# AFE.net
KiCad netlist of a schematic drawn in Altium Designer
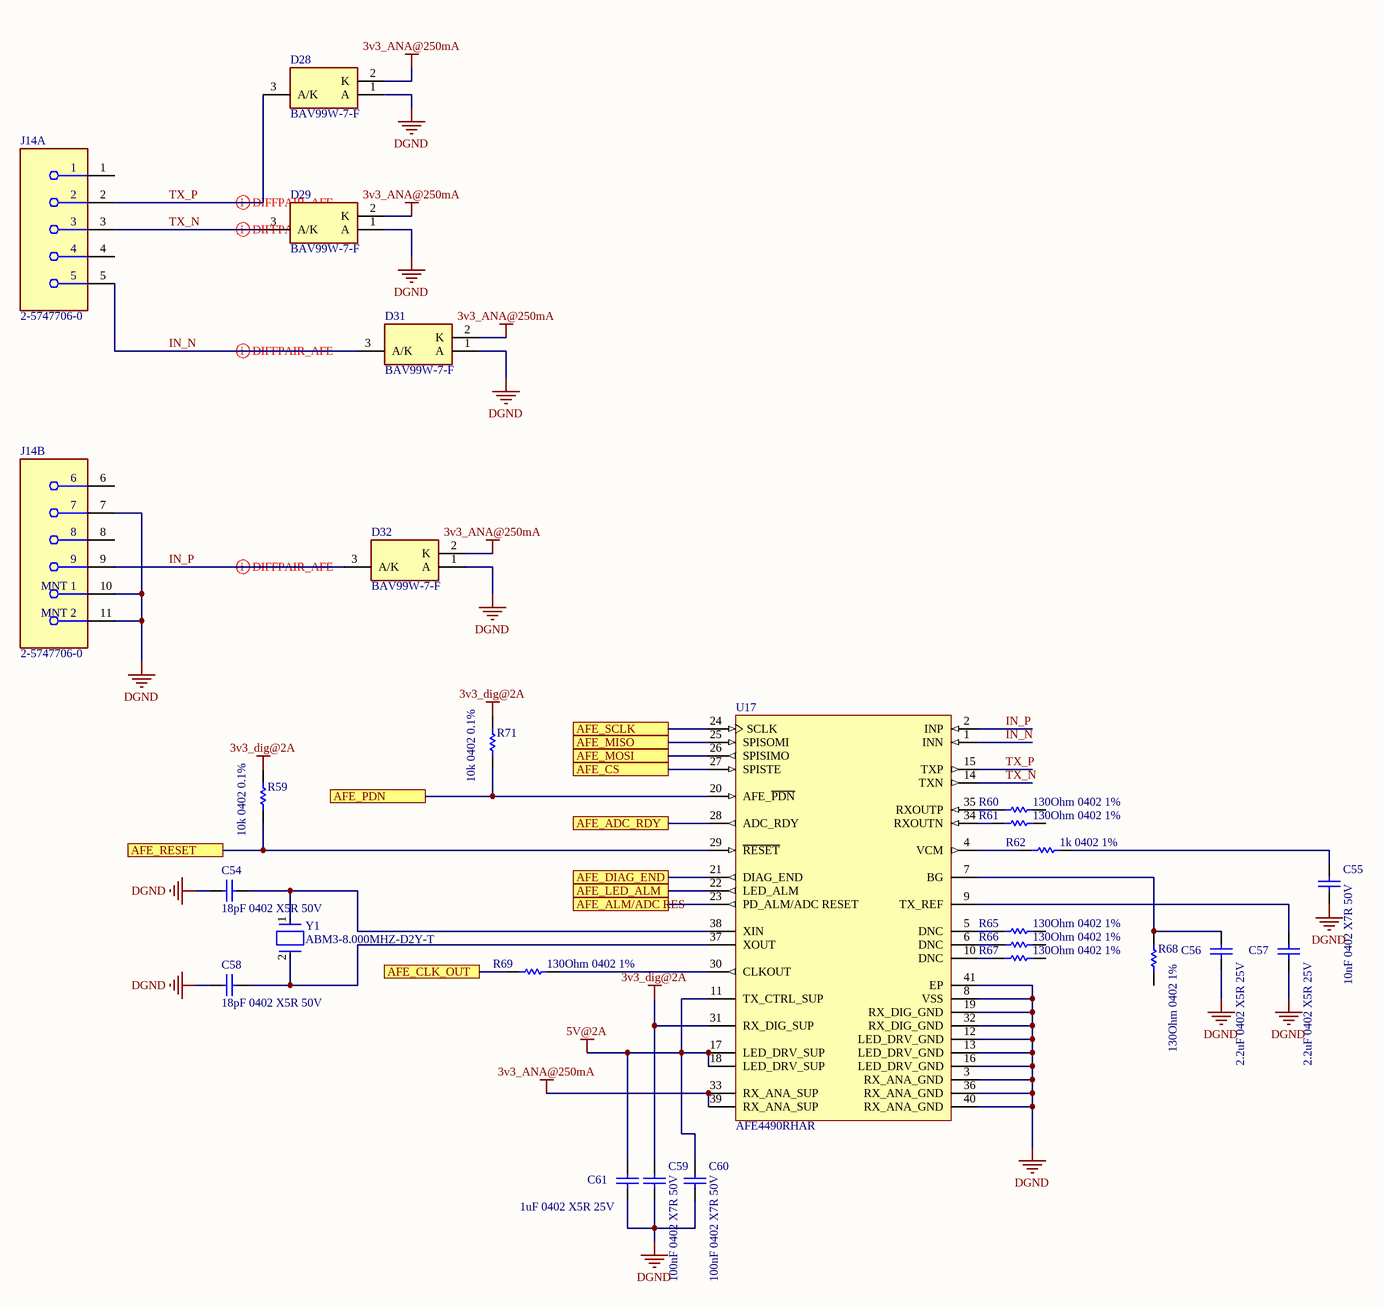
[diagram p0: AFE.SchDoc]

(export (version "E")
  (design (tool "Eeschema 10.0.6"))
  (components
    (comp (ref "C54")
      (value "18pF 0402 X5R 50V")
      (footprint "CAPC1005X55X25NL5T10")
      (libsource (lib "Altium Content Vault") (part "CAP-NP-2"))
    )
    (comp (ref "C55")
      (value "10nF 0402 X7R 50V")
      (footprint "CAPC1005X55X25NL5T10")
      (libsource (lib "Altium Content Vault") (part "CAP-NP-2"))
    )
    (comp (ref "C56")
      (value "2.2uF 0402 X5R 25V")
      (footprint "CAPC1005X55X25NL5T10")
      (libsource (lib "Altium Content Vault") (part "CAP-NP-2"))
    )
    (comp (ref "C57")
      (value "2.2uF 0402 X5R 25V")
      (footprint "CAPC1005X55X25NL5T10")
      (libsource (lib "Altium Content Vault") (part "CAP-NP-2"))
    )
    (comp (ref "C58")
      (value "18pF 0402 X5R 50V")
      (footprint "CAPC1005X55X25NL5T10")
      (libsource (lib "Altium Content Vault") (part "CAP-NP-2"))
    )
    (comp (ref "C59")
      (value "100nF 0402 X7R 50V")
      (footprint "CAPC1005X55X25NL5T10")
      (libsource (lib "Altium Content Vault") (part "CAP-NP-2"))
    )
    (comp (ref "C60")
      (value "100nF 0402 X7R 50V")
      (footprint "CAPC1005X55X25NL5T10")
      (libsource (lib "Altium Content Vault") (part "CAP-NP-2"))
    )
    (comp (ref "C61")
      (value "1uF 0402 X5R 25V")
      (footprint "CAPC1005X55X25NL5T10")
      (libsource (lib "Altium Content Vault") (part "CAP-NP-2"))
    )
    (comp (ref "D28")
      (value "BAV99W-7-F")
      (footprint "SamacSys:SOT65P210X110-3N")
      (description "Diode")
      (fields (field (name "MOUSER PART NUMBER") "621-BAV99W-F"))
      (libsource (lib "*") (part "BAV99W-7-F"))
    )
    (comp (ref "D29")
      (value "BAV99W-7-F")
      (footprint "SamacSys:SOT65P210X110-3N")
      (description "Diode")
      (fields (field (name "MOUSER PART NUMBER") "621-BAV99W-F"))
      (libsource (lib "*") (part "BAV99W-7-F"))
    )
    (comp (ref "D31")
      (value "BAV99W-7-F")
      (footprint "SamacSys:SOT65P210X110-3N")
      (description "Diode")
      (fields (field (name "MOUSER PART NUMBER") "621-BAV99W-F"))
      (libsource (lib "*") (part "BAV99W-7-F"))
    )
    (comp (ref "D32")
      (value "BAV99W-7-F")
      (footprint "SamacSys:SOT65P210X110-3N")
      (description "Diode")
      (fields (field (name "MOUSER PART NUMBER") "621-BAV99W-F"))
      (libsource (lib "*") (part "BAV99W-7-F"))
    )
    (comp (ref "J14")
      (value "2-5747706-0")
      (footprint "FP-2-5747706-0-MFG")
      (description "CONN D-SUB RCPT 9POS VERT SOLDER")
      (fields
        (field (name "OCTOPART") "https://octopart.com/2-5747706-0-te+connectivity-39499683")
        (field (name "MANUFACTURER") "TE Connectivity")
      )
      (libsource (lib "Altium Content Vault") (part "05b08df3a4487cf48e63ed58a2c51a6"))
    )
    (comp (ref "R59")
      (value "10k 0402 0.1%")
      (footprint "RESC1005X40X25ML05T10")
      (libsource (lib "Altium Content Vault") (part "RES"))
    )
    (comp (ref "R60")
      (value "130Ohm 0402 1%")
      (footprint "RESC1005X40X25ML05T10")
      (libsource (lib "Altium Content Vault") (part "RES"))
    )
    (comp (ref "R61")
      (value "130Ohm 0402 1%")
      (footprint "RESC1005X40X25ML05T10")
      (libsource (lib "Altium Content Vault") (part "RES"))
    )
    (comp (ref "R62")
      (value "1k 0402 1%")
      (footprint "RESC1005X40X25ML05T10")
      (libsource (lib "Altium Content Vault") (part "RES"))
    )
    (comp (ref "R65")
      (value "130Ohm 0402 1%")
      (footprint "RESC1005X40X25ML05T10")
      (libsource (lib "Altium Content Vault") (part "RES"))
    )
    (comp (ref "R66")
      (value "130Ohm 0402 1%")
      (footprint "RESC1005X40X25ML05T10")
      (libsource (lib "Altium Content Vault") (part "RES"))
    )
    (comp (ref "R67")
      (value "130Ohm 0402 1%")
      (footprint "RESC1005X40X25ML05T10")
      (libsource (lib "Altium Content Vault") (part "RES"))
    )
    (comp (ref "R68")
      (value "130Ohm 0402 1%")
      (footprint "RESC1005X40X25ML05T10")
      (libsource (lib "Altium Content Vault") (part "RES"))
    )
    (comp (ref "R69")
      (value "130Ohm 0402 1%")
      (footprint "RESC1005X40X25ML05T10")
      (libsource (lib "Altium Content Vault") (part "RES"))
    )
    (comp (ref "R71")
      (value "10k 0402 0.1%")
      (footprint "RESC1005X40X25ML05T10")
      (libsource (lib "Altium Content Vault") (part "RES"))
    )
    (comp (ref "U17")
      (value "AFE4490RHAR")
      (footprint "RHA0040B_V")
      (fields (field (name "MANUFACTURER") "Texas Instruments"))
      (libsource (lib "Altium Content Vault") (part "TI-AFE4490-RHA-40"))
    )
    (comp (ref "Y1")
      (value "ABM3-8.000MHZ-D2Y-T")
      (footprint "FP-ABM3-MFG")
      (description "Crystal 8MHz ±20ppm 18pF SMD-2 5mm x 3.2mm")
      (fields (field (name "TOLERANCE") "20ppm"))
      (libsource (lib "Altium Content Vault") (part "c23a69dc6c9e2f18f2079038eb95dd1"))
    )
  )
  (nets
    (net (code "1") (name "/AFE_ADC_RDY") (class "Default")
      (node (ref "U17") (pin "28") (pinfunction "ADC_RDY_28") (pintype "output"))
    )
    (net (code "2") (name "/AFE_ALM{slash}ADC RES") (class "Default")
      (node (ref "U17") (pin "23") (pinfunction "PD_ALM/ADC_RESET_23") (pintype "output"))
    )
    (net (code "3") (name "/AFE_CLK_OUT") (class "Default")
      (node (ref "R69") (pin "2") (pinfunction "2_2") (pintype "passive"))
    )
    (net (code "4") (name "/AFE_CS") (class "Default")
      (node (ref "U17") (pin "27") (pinfunction "SPISTE_27") (pintype "input"))
    )
    (net (code "5") (name "/AFE_DIAG_END") (class "Default")
      (node (ref "U17") (pin "21") (pinfunction "DIAG_END_21") (pintype "output"))
    )
    (net (code "6") (name "/AFE_LED_ALM") (class "Default")
      (node (ref "U17") (pin "22") (pinfunction "LED_ALM_22") (pintype "output"))
    )
    (net (code "7") (name "/AFE_MISO") (class "Default")
      (node (ref "U17") (pin "25") (pinfunction "SPISOMI_25") (pintype "input"))
    )
    (net (code "8") (name "/AFE_MOSI") (class "Default")
      (node (ref "U17") (pin "26") (pinfunction "SPISIMO_26") (pintype "output"))
    )
    (net (code "9") (name "/AFE_PDN") (class "Default")
      (node (ref "R71") (pin "1") (pinfunction "1_1") (pintype "passive"))
      (node (ref "U17") (pin "20") (pinfunction "AFE_~{PDN}_20") (pintype "input"))
    )
    (net (code "10") (name "/AFE_RESET") (class "Default")
      (node (ref "R59") (pin "1") (pinfunction "1_1") (pintype "passive"))
      (node (ref "U17") (pin "29") (pinfunction "~{RESET}_29") (pintype "input"))
    )
    (net (code "11") (name "/AFE_SCLK") (class "Default")
      (node (ref "U17") (pin "24") (pinfunction "SCLK_24") (pintype "input"))
    )
    (net (code "12") (name "/IN_N") (class "Default")
      (node (ref "D31") (pin "3") (pinfunction "A/K_3") (pintype "passive"))
      (node (ref "J14") (pin "5") (pinfunction "5_5") (pintype "passive"))
      (node (ref "U17") (pin "1") (pinfunction "INN_1") (pintype "input"))
    )
    (net (code "13") (name "/IN_P") (class "Default")
      (node (ref "D32") (pin "3") (pinfunction "A/K_3") (pintype "passive"))
      (node (ref "J14") (pin "9") (pinfunction "9_9") (pintype "passive"))
      (node (ref "U17") (pin "2") (pinfunction "INP_2") (pintype "input"))
    )
    (net (code "14") (name "/TX_N") (class "Default")
      (node (ref "D29") (pin "3") (pinfunction "A/K_3") (pintype "passive"))
      (node (ref "J14") (pin "3") (pinfunction "3_3") (pintype "passive"))
      (node (ref "U17") (pin "14") (pinfunction "TXN_14") (pintype "output"))
    )
    (net (code "15") (name "/TX_P") (class "Default")
      (node (ref "D28") (pin "3") (pinfunction "A/K_3") (pintype "passive"))
      (node (ref "J14") (pin "2") (pinfunction "2_2") (pintype "passive"))
      (node (ref "U17") (pin "15") (pinfunction "TXP_15") (pintype "output"))
    )
    (net (code "16") (name "3v3_ANA@250mA") (class "Default")
      (node (ref "D28") (pin "2") (pinfunction "K_2") (pintype "passive"))
      (node (ref "D29") (pin "2") (pinfunction "K_2") (pintype "passive"))
      (node (ref "D31") (pin "2") (pinfunction "K_2") (pintype "passive"))
      (node (ref "D32") (pin "2") (pinfunction "K_2") (pintype "passive"))
      (node (ref "U17") (pin "33") (pinfunction "RX_ANA_SUP_33") (pintype "power_in"))
      (node (ref "U17") (pin "39") (pinfunction "RX_ANA_SUP_39") (pintype "power_in"))
    )
    (net (code "17") (name "3v3_dig@2A") (class "Default")
      (node (ref "C59") (pin "2") (pinfunction "2_2") (pintype "passive"))
      (node (ref "R59") (pin "2") (pinfunction "2_2") (pintype "passive"))
      (node (ref "R71") (pin "2") (pinfunction "2_2") (pintype "passive"))
      (node (ref "U17") (pin "31") (pinfunction "RX_DIG_SUP_31") (pintype "power_in"))
    )
    (net (code "18") (name "5V@2A") (class "Default")
      (node (ref "C60") (pin "2") (pinfunction "2_2") (pintype "passive"))
      (node (ref "C61") (pin "2") (pinfunction "2_2") (pintype "passive"))
      (node (ref "U17") (pin "11") (pinfunction "TX_CTRL_SUP_11") (pintype "power_in"))
      (node (ref "U17") (pin "17") (pinfunction "LED_DRV_SUP_17") (pintype "power_in"))
      (node (ref "U17") (pin "18") (pinfunction "LED_DRV_SUP_18") (pintype "power_in"))
    )
    (net (code "19") (name "DGND") (class "Default")
      (node (ref "C54") (pin "1") (pinfunction "1_1") (pintype "passive"))
      (node (ref "C55") (pin "1") (pinfunction "1_1") (pintype "passive"))
      (node (ref "C56") (pin "1") (pinfunction "1_1") (pintype "passive"))
      (node (ref "C57") (pin "1") (pinfunction "1_1") (pintype "passive"))
      (node (ref "C58") (pin "1") (pinfunction "1_1") (pintype "passive"))
      (node (ref "C59") (pin "1") (pinfunction "1_1") (pintype "passive"))
      (node (ref "C60") (pin "1") (pinfunction "1_1") (pintype "passive"))
      (node (ref "C61") (pin "1") (pinfunction "1_1") (pintype "passive"))
      (node (ref "D28") (pin "1") (pinfunction "A_1") (pintype "passive"))
      (node (ref "D29") (pin "1") (pinfunction "A_1") (pintype "passive"))
      (node (ref "D31") (pin "1") (pinfunction "A_1") (pintype "passive"))
      (node (ref "D32") (pin "1") (pinfunction "A_1") (pintype "passive"))
      (node (ref "J14") (pin "10") (pinfunction "MNT_1_10") (pintype "passive"))
      (node (ref "J14") (pin "11") (pinfunction "MNT_2_11") (pintype "passive"))
      (node (ref "J14") (pin "7") (pinfunction "7_7") (pintype "passive"))
      (node (ref "U17") (pin "12") (pinfunction "LED_DRV_GND_12") (pintype "power_in"))
      (node (ref "U17") (pin "13") (pinfunction "LED_DRV_GND_13") (pintype "power_in"))
      (node (ref "U17") (pin "16") (pinfunction "LED_DRV_GND_16") (pintype "power_in"))
      (node (ref "U17") (pin "19") (pinfunction "RX_DIG_GND_19") (pintype "power_in"))
      (node (ref "U17") (pin "3") (pinfunction "RX_ANA_GND_3") (pintype "power_in"))
      (node (ref "U17") (pin "32") (pinfunction "RX_DIG_GND_32") (pintype "power_in"))
      (node (ref "U17") (pin "36") (pinfunction "RX_ANA_GND_36") (pintype "power_in"))
      (node (ref "U17") (pin "40") (pinfunction "RX_ANA_GND_40") (pintype "power_in"))
      (node (ref "U17") (pin "41") (pinfunction "EP_41") (pintype "passive"))
      (node (ref "U17") (pin "8") (pinfunction "VSS_8") (pintype "power_in"))
    )
    (net (code "20") (name "Net-(C55-Pad2)") (class "Default")
      (node (ref "C55") (pin "2") (pinfunction "2_2") (pintype "passive"))
      (node (ref "R62") (pin "1") (pinfunction "1_1") (pintype "passive"))
    )
    (net (code "21") (name "Net-(R65-Pad2)") (class "Default")
      (node (ref "R65") (pin "2") (pinfunction "2_2") (pintype "passive"))
      (node (ref "U17") (pin "5") (pinfunction "DNC_5") (pintype "passive"))
    )
    (net (code "22") (name "Net-(R66-Pad2)") (class "Default")
      (node (ref "R66") (pin "2") (pinfunction "2_2") (pintype "passive"))
      (node (ref "U17") (pin "6") (pinfunction "DNC_6") (pintype "passive"))
    )
    (net (code "23") (name "Net-(R67-Pad2)") (class "Default")
      (node (ref "R67") (pin "2") (pinfunction "2_2") (pintype "passive"))
      (node (ref "U17") (pin "10") (pinfunction "DNC_10") (pintype "passive"))
    )
    (net (code "24") (name "Net-(U17-BG)") (class "Default")
      (node (ref "C56") (pin "2") (pinfunction "2_2") (pintype "passive"))
      (node (ref "R68") (pin "2") (pinfunction "2_2") (pintype "passive"))
      (node (ref "U17") (pin "7") (pinfunction "BG_7") (pintype "passive"))
    )
    (net (code "25") (name "Net-(U17-CLKOUT)") (class "Default")
      (node (ref "R69") (pin "1") (pinfunction "1_1") (pintype "passive"))
      (node (ref "U17") (pin "30") (pinfunction "CLKOUT_30") (pintype "output"))
    )
    (net (code "26") (name "Net-(U17-RXOUTN)") (class "Default")
      (node (ref "R61") (pin "2") (pinfunction "2_2") (pintype "passive"))
      (node (ref "U17") (pin "34") (pinfunction "RXOUTN_34") (pintype "input"))
    )
    (net (code "27") (name "Net-(U17-RXOUTP)") (class "Default")
      (node (ref "R60") (pin "2") (pinfunction "2_2") (pintype "passive"))
      (node (ref "U17") (pin "35") (pinfunction "RXOUTP_35") (pintype "input"))
    )
    (net (code "28") (name "Net-(U17-TX_REF)") (class "Default")
      (node (ref "C57") (pin "2") (pinfunction "2_2") (pintype "passive"))
      (node (ref "U17") (pin "9") (pinfunction "TX_REF_9") (pintype "passive"))
    )
    (net (code "29") (name "Net-(U17-VCM)") (class "Default")
      (node (ref "R62") (pin "2") (pinfunction "2_2") (pintype "passive"))
      (node (ref "U17") (pin "4") (pinfunction "VCM_4") (pintype "output"))
    )
    (net (code "30") (name "Net-(U17-XIN)") (class "Default")
      (node (ref "C54") (pin "2") (pinfunction "2_2") (pintype "passive"))
      (node (ref "U17") (pin "38") (pinfunction "XIN_38") (pintype "passive"))
      (node (ref "Y1") (pin "1") (pinfunction "1_1") (pintype "passive"))
    )
    (net (code "31") (name "Net-(U17-XOUT)") (class "Default")
      (node (ref "C58") (pin "2") (pinfunction "2_2") (pintype "passive"))
      (node (ref "U17") (pin "37") (pinfunction "XOUT_37") (pintype "passive"))
      (node (ref "Y1") (pin "2") (pinfunction "2_2") (pintype "passive"))
    )
    (net (code "32") (name "unconnected-(J14-Pad1)") (class "Default")
      (node (ref "J14") (pin "1") (pinfunction "1_1") (pintype "passive"))
    )
    (net (code "33") (name "unconnected-(J14-Pad4)") (class "Default")
      (node (ref "J14") (pin "4") (pinfunction "4_4") (pintype "passive"))
    )
    (net (code "34") (name "unconnected-(J14-Pad6)") (class "Default")
      (node (ref "J14") (pin "6") (pinfunction "6_6") (pintype "passive"))
    )
    (net (code "35") (name "unconnected-(J14-Pad8)") (class "Default")
      (node (ref "J14") (pin "8") (pinfunction "8_8") (pintype "passive"))
    )
    (net (code "36") (name "unconnected-(R60-Pad1)") (class "Default")
      (node (ref "R60") (pin "1") (pinfunction "1_1") (pintype "passive"))
    )
    (net (code "37") (name "unconnected-(R61-Pad1)") (class "Default")
      (node (ref "R61") (pin "1") (pinfunction "1_1") (pintype "passive"))
    )
    (net (code "38") (name "unconnected-(R65-Pad1)") (class "Default")
      (node (ref "R65") (pin "1") (pinfunction "1_1") (pintype "passive"))
    )
    (net (code "39") (name "unconnected-(R66-Pad1)") (class "Default")
      (node (ref "R66") (pin "1") (pinfunction "1_1") (pintype "passive"))
    )
    (net (code "40") (name "unconnected-(R67-Pad1)") (class "Default")
      (node (ref "R67") (pin "1") (pinfunction "1_1") (pintype "passive"))
    )
    (net (code "41") (name "unconnected-(R68-Pad1)") (class "Default")
      (node (ref "R68") (pin "1") (pinfunction "1_1") (pintype "passive"))
    )
  )
)
